# SparkFun_NanoBeacon_Development_Board_-_.net
KiCad netlist of a schematic drawn in EAGLE
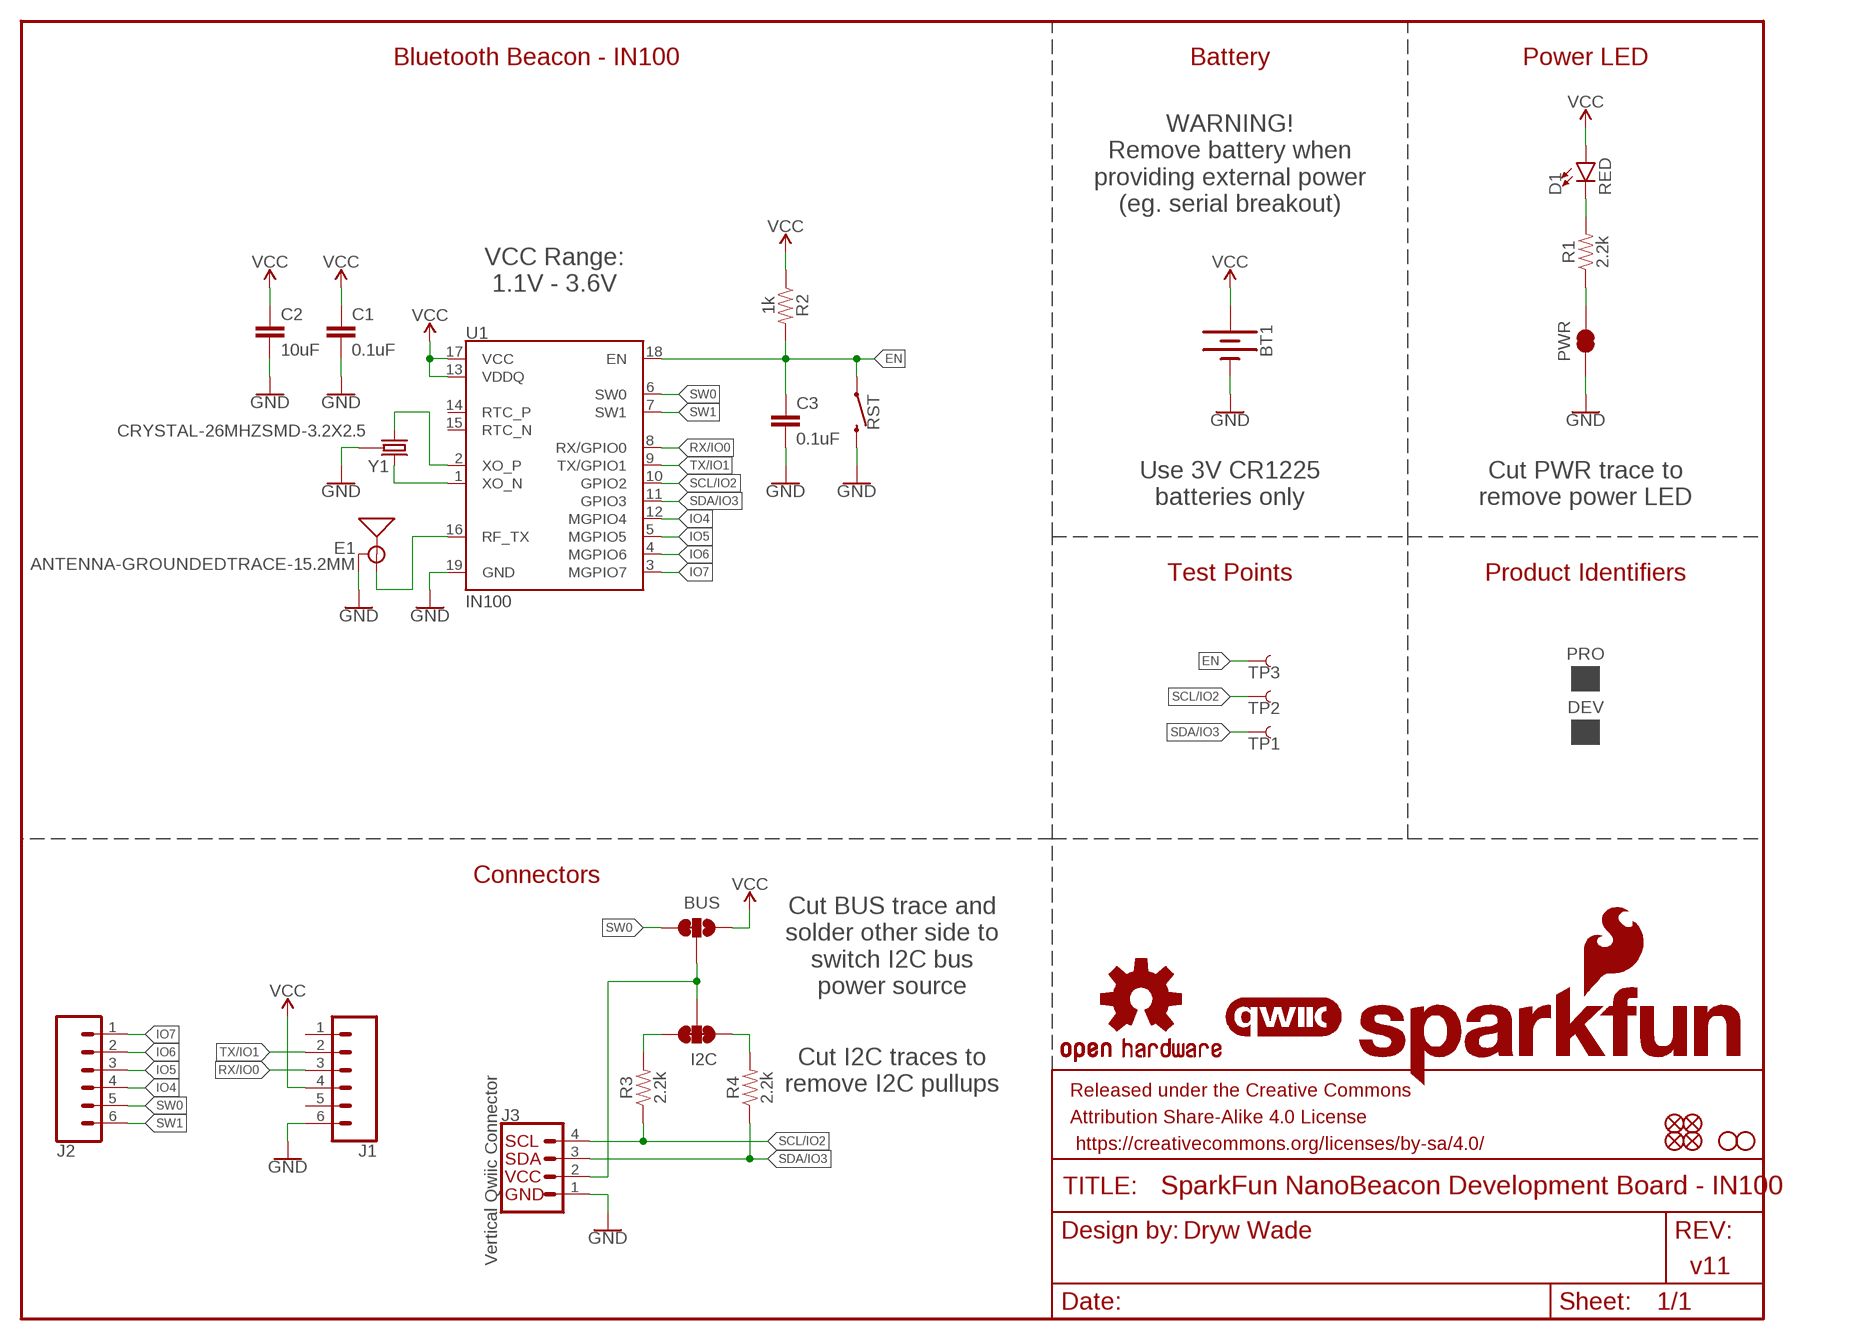
[diagram p0: schematic, sheet 1]

(export (version "E")
  (design (tool "Eeschema 10.0.6"))
  (components
    (comp (ref "BT1")
      (value "BATTERY-12MM_SMD")
      (footprint "eagle-import:BATTCON_12MM")
      (libsource (lib "eagle-import") (part "BATTERY-12MM_SMD"))
    )
    (comp (ref "BUS")
      (value "JUMPER-SMT_3_1-NC_TRACE_SILK")
      (footprint "eagle-import:SMT-JUMPER_3_1-NC_TRACE_SILK")
      (libsource (lib "eagle-import") (part "JUMPER-SMT_3_1-NC_TRACE_SILK"))
    )
    (comp (ref "C1")
      (value "0.1uF")
      (footprint "eagle-import:0402-TIGHT")
      (libsource (lib "eagle-import") (part "0.1UF-0402T-6.3V-10%-X7R"))
    )
    (comp (ref "C2")
      (value "10uF")
      (footprint "eagle-import:0402-TIGHT")
      (libsource (lib "eagle-import") (part "10UF-0402T-6.3V-20%"))
    )
    (comp (ref "C3")
      (value "0.1uF")
      (footprint "eagle-import:0402-TIGHT")
      (libsource (lib "eagle-import") (part "0.1UF-0402T-6.3V-10%-X7R"))
    )
    (comp (ref "D1")
      (value "RED")
      (footprint "eagle-import:LED-0402")
      (libsource (lib "eagle-import") (part "LED-RED_0402"))
    )
    (comp (ref "DEV")
      (value "PROD_ID_PASTE_SILK")
      (footprint "eagle-import:PRODUCT_IDENT_PASTE_SILK")
      (libsource (lib "eagle-import") (part "PROD_ID_PASTE_SILK"))
    )
    (comp (ref "E1")
      (value "ANTENNA-GROUNDEDTRACE-15.2MM")
      (footprint "eagle-import:TRACE_ANTENNA_2.4GHZ_15.2MM")
      (libsource (lib "eagle-import") (part "ANTENNA-GROUNDEDTRACE-15.2MM"))
    )
    (comp (ref "FD1")
      (value "FIDUCIAL1X2")
      (footprint "eagle-import:FIDUCIAL-1X2")
      (libsource (lib "eagle-import") (part "FIDUCIAL1X2"))
    )
    (comp (ref "FD2")
      (value "FIDUCIAL1X2")
      (footprint "eagle-import:FIDUCIAL-1X2")
      (libsource (lib "eagle-import") (part "FIDUCIAL1X2"))
    )
    (comp (ref "FD3")
      (value "FIDUCIAL1X2")
      (footprint "eagle-import:FIDUCIAL-1X2")
      (libsource (lib "eagle-import") (part "FIDUCIAL1X2"))
    )
    (comp (ref "FD4")
      (value "FIDUCIAL1X2")
      (footprint "eagle-import:FIDUCIAL-1X2")
      (libsource (lib "eagle-import") (part "FIDUCIAL1X2"))
    )
    (comp (ref "FRAME1")
      (value "FRAME-LETTER")
      (footprint "eagle-import:CREATIVE_COMMONS")
      (libsource (lib "eagle-import") (part "FRAME-LETTER"))
    )
    (comp (ref "H1")
      (value "STAND-OFF")
      (footprint "eagle-import:STAND-OFF")
      (libsource (lib "eagle-import") (part "STAND-OFF"))
    )
    (comp (ref "H2")
      (value "STAND-OFF")
      (footprint "eagle-import:STAND-OFF")
      (libsource (lib "eagle-import") (part "STAND-OFF"))
    )
    (comp (ref "I2C")
      (value "JUMPER-SMT_3_2-NC_TRACE_SILK")
      (footprint "eagle-import:SMT-JUMPER_3_2-NC_TRACE_SILK")
      (libsource (lib "eagle-import") (part "JUMPER-SMT_3_2-NC_TRACE_SILK"))
    )
    (comp (ref "J1")
      (value "CONN_06NO_SILK_NO_POP")
      (footprint "eagle-import:1X06_NO_SILK")
      (libsource (lib "eagle-import") (part "CONN_06NO_SILK_NO_POP"))
    )
    (comp (ref "J2")
      (value "CONN_06NO_SILK_NO_POP")
      (footprint "eagle-import:1X06_NO_SILK")
      (libsource (lib "eagle-import") (part "CONN_06NO_SILK_NO_POP"))
    )
    (comp (ref "J3")
      (value "Vertical Qwiic Connector")
      (footprint "eagle-import:JST04_1MM_VERT")
      (libsource (lib "eagle-import") (part "QWIIC_CONNECTOR"))
    )
    (comp (ref "LOGO1")
      (value "OSHW-LOGOS")
      (footprint "eagle-import:OSHW-LOGO-S")
      (libsource (lib "eagle-import") (part "OSHW-LOGOS"))
    )
    (comp (ref "LOGO2")
      (value "SFE_LOGO_NAME_FLAME.1_INCH")
      (footprint "eagle-import:SFE_LOGO_NAME_FLAME_.1")
      (libsource (lib "eagle-import") (part "SFE_LOGO_NAME_FLAME.1_INCH"))
    )
    (comp (ref "LOGO3")
      (value "QWIIC_LOGO_3MM")
      (footprint "eagle-import:QWIIC_3MM")
      (libsource (lib "eagle-import") (part "QWIIC_LOGO_3MM"))
    )
    (comp (ref "PRO")
      (value "PROD_ID_PASTE_SILK")
      (footprint "eagle-import:PRODUCT_IDENT_PASTE_SILK")
      (libsource (lib "eagle-import") (part "PROD_ID_PASTE_SILK"))
    )
    (comp (ref "PWR")
      (value "JUMPER-SMT_2_NC_TRACE_SILK")
      (footprint "eagle-import:SMT-JUMPER_2_NC_TRACE_SILK")
      (libsource (lib "eagle-import") (part "JUMPER-SMT_2_NC_TRACE_SILK"))
    )
    (comp (ref "R1")
      (value "2.2k")
      (footprint "eagle-import:0402-TIGHT")
      (libsource (lib "eagle-import") (part "2.2KOHM-0402T-1/16W-1%"))
    )
    (comp (ref "R2")
      (value "1k")
      (footprint "eagle-import:0402-TIGHT")
      (libsource (lib "eagle-import") (part "1KOHM-0402T-1/16W-1%"))
    )
    (comp (ref "R3")
      (value "2.2k")
      (footprint "eagle-import:0402-TIGHT")
      (libsource (lib "eagle-import") (part "2.2KOHM-0402T-1/16W-1%"))
    )
    (comp (ref "R4")
      (value "2.2k")
      (footprint "eagle-import:0402-TIGHT")
      (libsource (lib "eagle-import") (part "2.2KOHM-0402T-1/16W-1%"))
    )
    (comp (ref "RST")
      (value "MOMENTARY-SWITCH-SPST-SMD-4.6X2.8MM")
      (footprint "eagle-import:TACTILE_SWITCH_SMD_4.6X2.8MM")
      (libsource (lib "eagle-import") (part "MOMENTARY-SWITCH-SPST-SMD-4.6X2.8MM"))
    )
    (comp (ref "TP1")
      (value "TEST-POINT3")
      (footprint "eagle-import:PAD.03X.03")
      (libsource (lib "eagle-import") (part "TEST-POINT3"))
    )
    (comp (ref "TP2")
      (value "TEST-POINT3")
      (footprint "eagle-import:PAD.03X.03")
      (libsource (lib "eagle-import") (part "TEST-POINT3"))
    )
    (comp (ref "TP3")
      (value "TEST-POINT3")
      (footprint "eagle-import:PAD.03X.03")
      (libsource (lib "eagle-import") (part "TEST-POINT3"))
    )
    (comp (ref "U1")
      (value "IN100")
      (footprint "eagle-import:IN100")
      (libsource (lib "eagle-import") (part "IN100"))
    )
    (comp (ref "Y1")
      (value "CRYSTAL-26MHZSMD-3.2X2.5")
      (footprint "eagle-import:CRYSTAL-SMD-3.2X2.5MM")
      (libsource (lib "eagle-import") (part "CRYSTAL-26MHZSMD-3.2X2.5"))
    )
  )
  (nets
    (net (code "1") (name "EN") (class "Default")
      (node (ref "C3") (pin "1") (pinfunction "1_1") (pintype "passive"))
      (node (ref "R2") (pin "2") (pinfunction "2_2") (pintype "passive"))
      (node (ref "RST") (pin "1") (pinfunction "1_1") (pintype "passive"))
      (node (ref "RST") (pin "2") (pinfunction "1_2") (pintype "passive"))
      (node (ref "TP3") (pin "1") (pinfunction "1_1") (pintype "bidirectional"))
      (node (ref "U1") (pin "18") (pinfunction "EN_18") (pintype "input"))
    )
    (net (code "2") (name "GND") (class "Default")
      (node (ref "BT1") (pin "GND") (pinfunction "-_GND") (pintype "power_in"))
      (node (ref "C1") (pin "2") (pinfunction "2_2") (pintype "passive"))
      (node (ref "C2") (pin "2") (pinfunction "2_2") (pintype "passive"))
      (node (ref "C3") (pin "2") (pinfunction "2_2") (pintype "passive"))
      (node (ref "E1") (pin "GND") (pinfunction "GND_GND") (pintype "bidirectional"))
      (node (ref "J1") (pin "6") (pinfunction "6_6") (pintype "passive"))
      (node (ref "J3") (pin "1") (pinfunction "1_1") (pintype "power_in"))
      (node (ref "PWR") (pin "1") (pinfunction "1_1") (pintype "passive"))
      (node (ref "RST") (pin "3") (pinfunction "2_3") (pintype "passive"))
      (node (ref "RST") (pin "4") (pinfunction "2_4") (pintype "passive"))
      (node (ref "U1") (pin "19") (pinfunction "GND_19") (pintype "power_in"))
      (node (ref "Y1") (pin "2") (pinfunction "GND_2") (pintype "power_in"))
      (node (ref "Y1") (pin "4") (pinfunction "GND_4") (pintype "power_in"))
    )
    (net (code "3") (name "IO4") (class "Default")
      (node (ref "J2") (pin "4") (pinfunction "4_4") (pintype "passive"))
      (node (ref "U1") (pin "12") (pinfunction "MGPIO4_12") (pintype "bidirectional"))
    )
    (net (code "4") (name "IO5") (class "Default")
      (node (ref "J2") (pin "3") (pinfunction "3_3") (pintype "passive"))
      (node (ref "U1") (pin "5") (pinfunction "MGPIO5_5") (pintype "bidirectional"))
    )
    (net (code "5") (name "IO6") (class "Default")
      (node (ref "J2") (pin "2") (pinfunction "2_2") (pintype "passive"))
      (node (ref "U1") (pin "4") (pinfunction "MGPIO6_4") (pintype "bidirectional"))
    )
    (net (code "6") (name "IO7") (class "Default")
      (node (ref "J2") (pin "1") (pinfunction "1_1") (pintype "passive"))
      (node (ref "U1") (pin "3") (pinfunction "MGPIO7_3") (pintype "bidirectional"))
    )
    (net (code "7") (name "Net-(BUS-Pad2)") (class "Default")
      (node (ref "BUS") (pin "2") (pinfunction "2_2") (pintype "passive"))
      (node (ref "I2C") (pin "2") (pinfunction "2_2") (pintype "passive"))
      (node (ref "J3") (pin "2") (pinfunction "2_2") (pintype "power_in"))
    )
    (net (code "8") (name "Net-(D1-PadC)") (class "Default")
      (node (ref "D1") (pin "C") (pinfunction "C_C") (pintype "passive"))
      (node (ref "R1") (pin "2") (pinfunction "2_2") (pintype "passive"))
    )
    (net (code "9") (name "Net-(E1-SIGNAL)") (class "Default")
      (node (ref "E1") (pin "ANT") (pinfunction "SIGNAL_ANT") (pintype "bidirectional"))
      (node (ref "U1") (pin "16") (pinfunction "RF_TX_16") (pintype "bidirectional"))
    )
    (net (code "10") (name "Net-(I2C-Pad1)") (class "Default")
      (node (ref "I2C") (pin "1") (pinfunction "1_1") (pintype "passive"))
      (node (ref "R4") (pin "2") (pinfunction "2_2") (pintype "passive"))
    )
    (net (code "11") (name "Net-(I2C-Pad3)") (class "Default")
      (node (ref "I2C") (pin "3") (pinfunction "3_3") (pintype "passive"))
      (node (ref "R3") (pin "2") (pinfunction "2_2") (pintype "passive"))
    )
    (net (code "12") (name "Net-(PWR-Pad2)") (class "Default")
      (node (ref "PWR") (pin "2") (pinfunction "2_2") (pintype "passive"))
      (node (ref "R1") (pin "1") (pinfunction "1_1") (pintype "passive"))
    )
    (net (code "13") (name "Net-(U1-XO_N)") (class "Default")
      (node (ref "U1") (pin "1") (pinfunction "XO_N_1") (pintype "bidirectional"))
      (node (ref "Y1") (pin "3") (pinfunction "2_3") (pintype "passive"))
    )
    (net (code "14") (name "Net-(U1-XO_P)") (class "Default")
      (node (ref "U1") (pin "2") (pinfunction "XO_P_2") (pintype "bidirectional"))
      (node (ref "Y1") (pin "1") (pinfunction "1_1") (pintype "passive"))
    )
    (net (code "15") (name "RX{slash}IO0") (class "Default")
      (node (ref "J1") (pin "3") (pinfunction "3_3") (pintype "passive"))
      (node (ref "U1") (pin "8") (pinfunction "RX/GPIO0_8") (pintype "bidirectional"))
    )
    (net (code "16") (name "SCL{slash}IO2") (class "Default")
      (node (ref "J3") (pin "4") (pinfunction "4_4") (pintype "passive"))
      (node (ref "R3") (pin "1") (pinfunction "1_1") (pintype "passive"))
      (node (ref "TP2") (pin "1") (pinfunction "1_1") (pintype "bidirectional"))
      (node (ref "U1") (pin "10") (pinfunction "GPIO2_10") (pintype "bidirectional"))
    )
    (net (code "17") (name "SDA{slash}IO3") (class "Default")
      (node (ref "J3") (pin "3") (pinfunction "3_3") (pintype "passive"))
      (node (ref "R4") (pin "1") (pinfunction "1_1") (pintype "passive"))
      (node (ref "TP1") (pin "1") (pinfunction "1_1") (pintype "bidirectional"))
      (node (ref "U1") (pin "11") (pinfunction "GPIO3_11") (pintype "bidirectional"))
    )
    (net (code "18") (name "SW0") (class "Default")
      (node (ref "BUS") (pin "3") (pinfunction "3_3") (pintype "passive"))
      (node (ref "J2") (pin "5") (pinfunction "5_5") (pintype "passive"))
      (node (ref "U1") (pin "6") (pinfunction "SW0_6") (pintype "output"))
    )
    (net (code "19") (name "SW1") (class "Default")
      (node (ref "J2") (pin "6") (pinfunction "6_6") (pintype "passive"))
      (node (ref "U1") (pin "7") (pinfunction "SW1_7") (pintype "output"))
    )
    (net (code "20") (name "TX{slash}IO1") (class "Default")
      (node (ref "J1") (pin "2") (pinfunction "2_2") (pintype "passive"))
      (node (ref "U1") (pin "9") (pinfunction "TX/GPIO1_9") (pintype "bidirectional"))
    )
    (net (code "21") (name "VCC") (class "Default")
      (node (ref "BT1") (pin "PWR@1") (pinfunction "+_PWR@1") (pintype "power_in"))
      (node (ref "BT1") (pin "PWR@2") (pinfunction "+_PWR@2") (pintype "power_in"))
      (node (ref "BUS") (pin "1") (pinfunction "1_1") (pintype "passive"))
      (node (ref "C1") (pin "1") (pinfunction "1_1") (pintype "passive"))
      (node (ref "C2") (pin "1") (pinfunction "1_1") (pintype "passive"))
      (node (ref "D1") (pin "A") (pinfunction "A_A") (pintype "passive"))
      (node (ref "J1") (pin "4") (pinfunction "4_4") (pintype "passive"))
      (node (ref "R2") (pin "1") (pinfunction "1_1") (pintype "passive"))
      (node (ref "U1") (pin "13") (pinfunction "VDDQ_13") (pintype "power_in"))
      (node (ref "U1") (pin "17") (pinfunction "VCC_17") (pintype "power_in"))
    )
    (net (code "22") (name "unconnected-(J1-Pad1)") (class "Default")
      (node (ref "J1") (pin "1") (pinfunction "1_1") (pintype "passive"))
    )
    (net (code "23") (name "unconnected-(J1-Pad5)") (class "Default")
      (node (ref "J1") (pin "5") (pinfunction "5_5") (pintype "passive"))
    )
    (net (code "24") (name "unconnected-(U1-RTC_N-Pad15)") (class "Default")
      (node (ref "U1") (pin "15") (pinfunction "RTC_N_15") (pintype "bidirectional"))
    )
    (net (code "25") (name "unconnected-(U1-RTC_P-Pad14)") (class "Default")
      (node (ref "U1") (pin "14") (pinfunction "RTC_P_14") (pintype "bidirectional"))
    )
  )
)
